# TDA2004.net
KiCad netlist of a schematic drawn in EAGLE
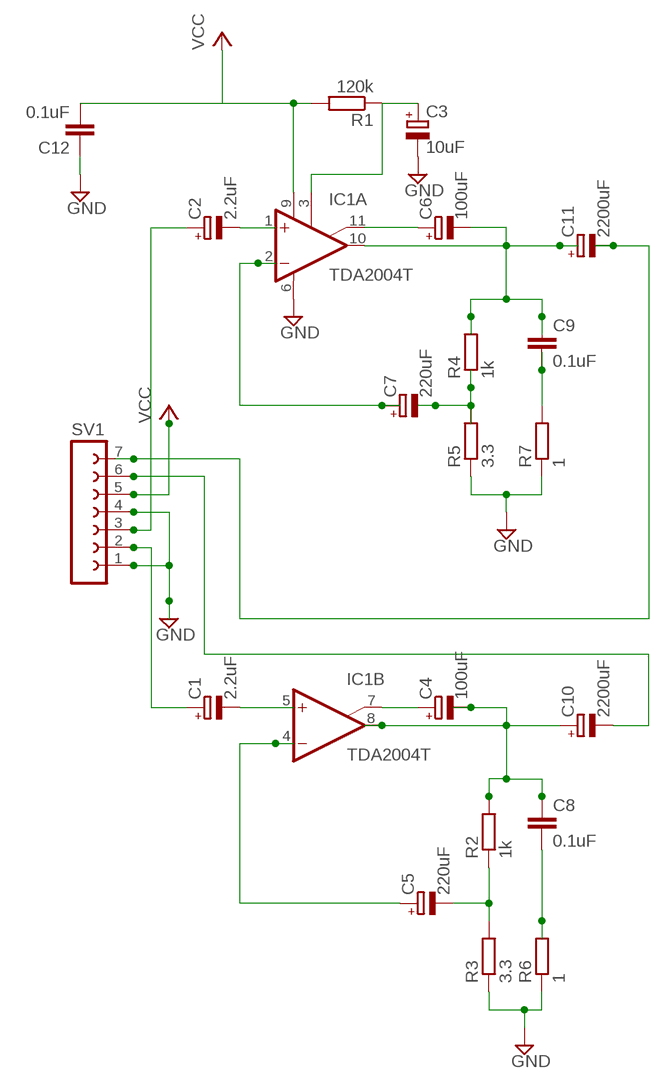
[diagram p0: schematic, sheet 1]

(export (version "E")
  (design (tool "Eeschema 10.0.6"))
  (components
    (comp (ref "C1")
      (value "2.2uF")
      (footprint "eagle-import:B45181B")
      (libsource (lib "eagle-import") (part "CPOL-EUB45181B"))
    )
    (comp (ref "C2")
      (value "2.2uF")
      (footprint "eagle-import:B45181B")
      (libsource (lib "eagle-import") (part "CPOL-EUB45181B"))
    )
    (comp (ref "C3")
      (value "10uF")
      (footprint "eagle-import:B45181B")
      (libsource (lib "eagle-import") (part "CPOL-EUB45181B"))
    )
    (comp (ref "C4")
      (value "100uF")
      (footprint "eagle-import:E2,5-5")
      (libsource (lib "eagle-import") (part "CPOL-EUE2.5-5"))
    )
    (comp (ref "C5")
      (value "220uF")
      (footprint "eagle-import:B45181B")
      (libsource (lib "eagle-import") (part "CPOL-EUB45181B"))
    )
    (comp (ref "C6")
      (value "100uF")
      (footprint "eagle-import:E2,5-5")
      (libsource (lib "eagle-import") (part "CPOL-EUE2.5-5"))
    )
    (comp (ref "C7")
      (value "220uF")
      (footprint "eagle-import:B45181B")
      (libsource (lib "eagle-import") (part "CPOL-EUB45181B"))
    )
    (comp (ref "C8")
      (value "0.1uF")
      (footprint "eagle-import:C025-024X044")
      (libsource (lib "eagle-import") (part "C-EU025-024X044"))
    )
    (comp (ref "C9")
      (value "0.1uF")
      (footprint "eagle-import:C025-024X044")
      (libsource (lib "eagle-import") (part "C-EU025-024X044"))
    )
    (comp (ref "C10")
      (value "2200uF")
      (footprint "eagle-import:E5-10,5")
      (libsource (lib "eagle-import") (part "CPOL-EUE5-10.5"))
    )
    (comp (ref "C11")
      (value "2200uF")
      (footprint "eagle-import:E5-10,5")
      (libsource (lib "eagle-import") (part "CPOL-EUE5-10.5"))
    )
    (comp (ref "C12")
      (value "0.1uF")
      (footprint "eagle-import:C025-024X044")
      (libsource (lib "eagle-import") (part "C-EU025-024X044"))
    )
    (comp (ref "IC1")
      (value "TDA2004T")
      (footprint "eagle-import:SIP11")
      (libsource (lib "eagle-import") (part "TDA2004T"))
    )
    (comp (ref "R1")
      (value "120k")
      (footprint "eagle-import:0207_10")
      (libsource (lib "eagle-import") (part "R-EU_0207/10"))
    )
    (comp (ref "R2")
      (value "1k")
      (footprint "eagle-import:0207_10")
      (libsource (lib "eagle-import") (part "R-EU_0207/10"))
    )
    (comp (ref "R3")
      (value "3.3")
      (footprint "eagle-import:0207_10")
      (libsource (lib "eagle-import") (part "R-EU_0207/10"))
    )
    (comp (ref "R4")
      (value "1k")
      (footprint "eagle-import:0207_10")
      (libsource (lib "eagle-import") (part "R-EU_0207/10"))
    )
    (comp (ref "R5")
      (value "3.3")
      (footprint "eagle-import:0207_10")
      (libsource (lib "eagle-import") (part "R-EU_0207/10"))
    )
    (comp (ref "R6")
      (value "1")
      (footprint "eagle-import:0207_10")
      (libsource (lib "eagle-import") (part "R-EU_0207/10"))
    )
    (comp (ref "R7")
      (value "1")
      (footprint "eagle-import:0207_10")
      (libsource (lib "eagle-import") (part "R-EU_0207/10"))
    )
    (comp (ref "SV1")
      (value "FE07-1")
      (footprint "eagle-import:FE07")
      (libsource (lib "eagle-import") (part "FE07-1"))
    )
  )
  (nets
    (net (code "1") (name "GND") (class "Default")
      (node (ref "C12") (pin "1") (pinfunction "1_1") (pintype "passive"))
      (node (ref "C3") (pin "-") (pinfunction "-_-") (pintype "passive"))
      (node (ref "IC1") (pin "6") (pinfunction "GND_6") (pintype "power_in"))
      (node (ref "R3") (pin "1") (pinfunction "1_1") (pintype "passive"))
      (node (ref "R5") (pin "1") (pinfunction "1_1") (pintype "passive"))
      (node (ref "R6") (pin "1") (pinfunction "1_1") (pintype "passive"))
      (node (ref "R7") (pin "1") (pinfunction "1_1") (pintype "passive"))
      (node (ref "SV1") (pin "1") (pinfunction "1_1") (pintype "passive"))
      (node (ref "SV1") (pin "4") (pinfunction "4_4") (pintype "passive"))
    )
    (net (code "2") (name "Net-(C1-Pad+)") (class "Default")
      (node (ref "C1") (pin "+") (pinfunction "+_+") (pintype "passive"))
      (node (ref "SV1") (pin "2") (pinfunction "2_2") (pintype "passive"))
    )
    (net (code "3") (name "Net-(C2-Pad+)") (class "Default")
      (node (ref "C2") (pin "+") (pinfunction "+_+") (pintype "passive"))
      (node (ref "SV1") (pin "3") (pinfunction "3_3") (pintype "passive"))
    )
    (net (code "4") (name "Net-(C5-Pad-)") (class "Default")
      (node (ref "C5") (pin "-") (pinfunction "-_-") (pintype "passive"))
      (node (ref "R2") (pin "1") (pinfunction "1_1") (pintype "passive"))
      (node (ref "R3") (pin "2") (pinfunction "2_2") (pintype "passive"))
    )
    (net (code "5") (name "Net-(C7-Pad-)") (class "Default")
      (node (ref "C7") (pin "-") (pinfunction "-_-") (pintype "passive"))
      (node (ref "R4") (pin "1") (pinfunction "1_1") (pintype "passive"))
      (node (ref "R5") (pin "2") (pinfunction "2_2") (pintype "passive"))
    )
    (net (code "6") (name "Net-(C8-Pad2)") (class "Default")
      (node (ref "C8") (pin "2") (pinfunction "2_2") (pintype "passive"))
      (node (ref "R6") (pin "2") (pinfunction "2_2") (pintype "passive"))
    )
    (net (code "7") (name "Net-(C9-Pad2)") (class "Default")
      (node (ref "C9") (pin "2") (pinfunction "2_2") (pintype "passive"))
      (node (ref "R7") (pin "2") (pinfunction "2_2") (pintype "passive"))
    )
    (net (code "8") (name "Net-(C10-Pad-)") (class "Default")
      (node (ref "C10") (pin "-") (pinfunction "-_-") (pintype "passive"))
      (node (ref "SV1") (pin "6") (pinfunction "6_6") (pintype "passive"))
    )
    (net (code "9") (name "Net-(C11-Pad-)") (class "Default")
      (node (ref "C11") (pin "-") (pinfunction "-_-") (pintype "passive"))
      (node (ref "SV1") (pin "7") (pinfunction "7_7") (pintype "passive"))
    )
    (net (code "10") (name "Net-(IC1A-+IN)") (class "Default")
      (node (ref "C2") (pin "-") (pinfunction "-_-") (pintype "passive"))
      (node (ref "IC1") (pin "1") (pinfunction "+IN_1") (pintype "input"))
    )
    (net (code "11") (name "Net-(IC1A--IN)") (class "Default")
      (node (ref "C7") (pin "+") (pinfunction "+_+") (pintype "passive"))
      (node (ref "IC1") (pin "2") (pinfunction "-IN_2") (pintype "input"))
    )
    (net (code "12") (name "Net-(IC1A-BTSP)") (class "Default")
      (node (ref "C6") (pin "+") (pinfunction "+_+") (pintype "passive"))
      (node (ref "IC1") (pin "11") (pinfunction "BTSP_11") (pintype "passive"))
    )
    (net (code "13") (name "Net-(IC1A-OUT)") (class "Default")
      (node (ref "C11") (pin "+") (pinfunction "+_+") (pintype "passive"))
      (node (ref "C6") (pin "-") (pinfunction "-_-") (pintype "passive"))
      (node (ref "C9") (pin "1") (pinfunction "1_1") (pintype "passive"))
      (node (ref "IC1") (pin "10") (pinfunction "OUT_10") (pintype "output"))
      (node (ref "R4") (pin "2") (pinfunction "2_2") (pintype "passive"))
    )
    (net (code "14") (name "Net-(IC1A-SVRR)") (class "Default")
      (node (ref "C3") (pin "+") (pinfunction "+_+") (pintype "passive"))
      (node (ref "IC1") (pin "3") (pinfunction "SVRR_3") (pintype "passive"))
      (node (ref "R1") (pin "1") (pinfunction "1_1") (pintype "passive"))
    )
    (net (code "15") (name "Net-(IC1B-+IN)") (class "Default")
      (node (ref "C1") (pin "-") (pinfunction "-_-") (pintype "passive"))
      (node (ref "IC1") (pin "5") (pinfunction "+IN_5") (pintype "input"))
    )
    (net (code "16") (name "Net-(IC1B--IN)") (class "Default")
      (node (ref "C5") (pin "+") (pinfunction "+_+") (pintype "passive"))
      (node (ref "IC1") (pin "4") (pinfunction "-IN_4") (pintype "input"))
    )
    (net (code "17") (name "Net-(IC1B-BTSP)") (class "Default")
      (node (ref "C4") (pin "+") (pinfunction "+_+") (pintype "passive"))
      (node (ref "IC1") (pin "7") (pinfunction "BTSP_7") (pintype "passive"))
    )
    (net (code "18") (name "Net-(IC1B-OUT)") (class "Default")
      (node (ref "C10") (pin "+") (pinfunction "+_+") (pintype "passive"))
      (node (ref "C4") (pin "-") (pinfunction "-_-") (pintype "passive"))
      (node (ref "C8") (pin "1") (pinfunction "1_1") (pintype "passive"))
      (node (ref "IC1") (pin "8") (pinfunction "OUT_8") (pintype "output"))
      (node (ref "R2") (pin "2") (pinfunction "2_2") (pintype "passive"))
    )
    (net (code "19") (name "VCC") (class "Default")
      (node (ref "C12") (pin "2") (pinfunction "2_2") (pintype "passive"))
      (node (ref "IC1") (pin "9") (pinfunction "V+_9") (pintype "power_in"))
      (node (ref "R1") (pin "2") (pinfunction "2_2") (pintype "passive"))
      (node (ref "SV1") (pin "5") (pinfunction "5_5") (pintype "passive"))
    )
  )
)
